# Tone_Control_Block.net
KiCad netlist of a schematic drawn in Altium Designer
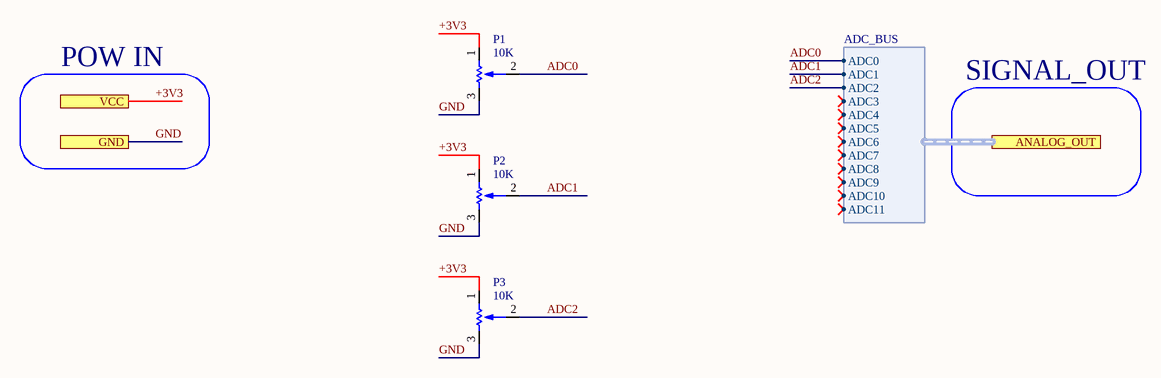
[diagram p0: Tone_Control_Block.SchDoc]

(export (version "E")
  (design (tool "Eeschema 10.0.6"))
  (components
    (comp (ref "P1")
      (value "10K")
      (footprint "POT-THT")
      (libsource (lib "LIB2022 - Passives") (part "POT-THT"))
    )
    (comp (ref "P2")
      (value "10K")
      (footprint "POT-THT")
      (libsource (lib "LIB2022 - Passives") (part "POT-THT"))
    )
    (comp (ref "P3")
      (value "10K")
      (footprint "POT-THT")
      (libsource (lib "LIB2022 - Passives") (part "POT-THT"))
    )
  )
  (nets
    (net (code "2") (name "/+3V3") (class "Default")
      (node (ref "P1") (pin "1") (pinfunction "1_1") (pintype "passive"))
      (node (ref "P2") (pin "1") (pinfunction "1_1") (pintype "passive"))
      (node (ref "P3") (pin "1") (pinfunction "1_1") (pintype "passive"))
    )
    (net (code "3") (name "/ADC0") (class "Default")
      (node (ref "P1") (pin "2") (pinfunction "2_2") (pintype "passive"))
    )
    (net (code "4") (name "/ADC1") (class "Default")
      (node (ref "P2") (pin "2") (pinfunction "2_2") (pintype "passive"))
    )
    (net (code "5") (name "/ADC2") (class "Default")
      (node (ref "P3") (pin "2") (pinfunction "2_2") (pintype "passive"))
    )
    (net (code "6") (name "/GND") (class "Default")
      (node (ref "P1") (pin "3") (pinfunction "3_3") (pintype "passive"))
      (node (ref "P2") (pin "3") (pinfunction "3_3") (pintype "passive"))
      (node (ref "P3") (pin "3") (pinfunction "3_3") (pintype "passive"))
    )
  )
)
